# Tastendruckverlaengerer_1.net
KiCad netlist of a schematic drawn in EAGLE
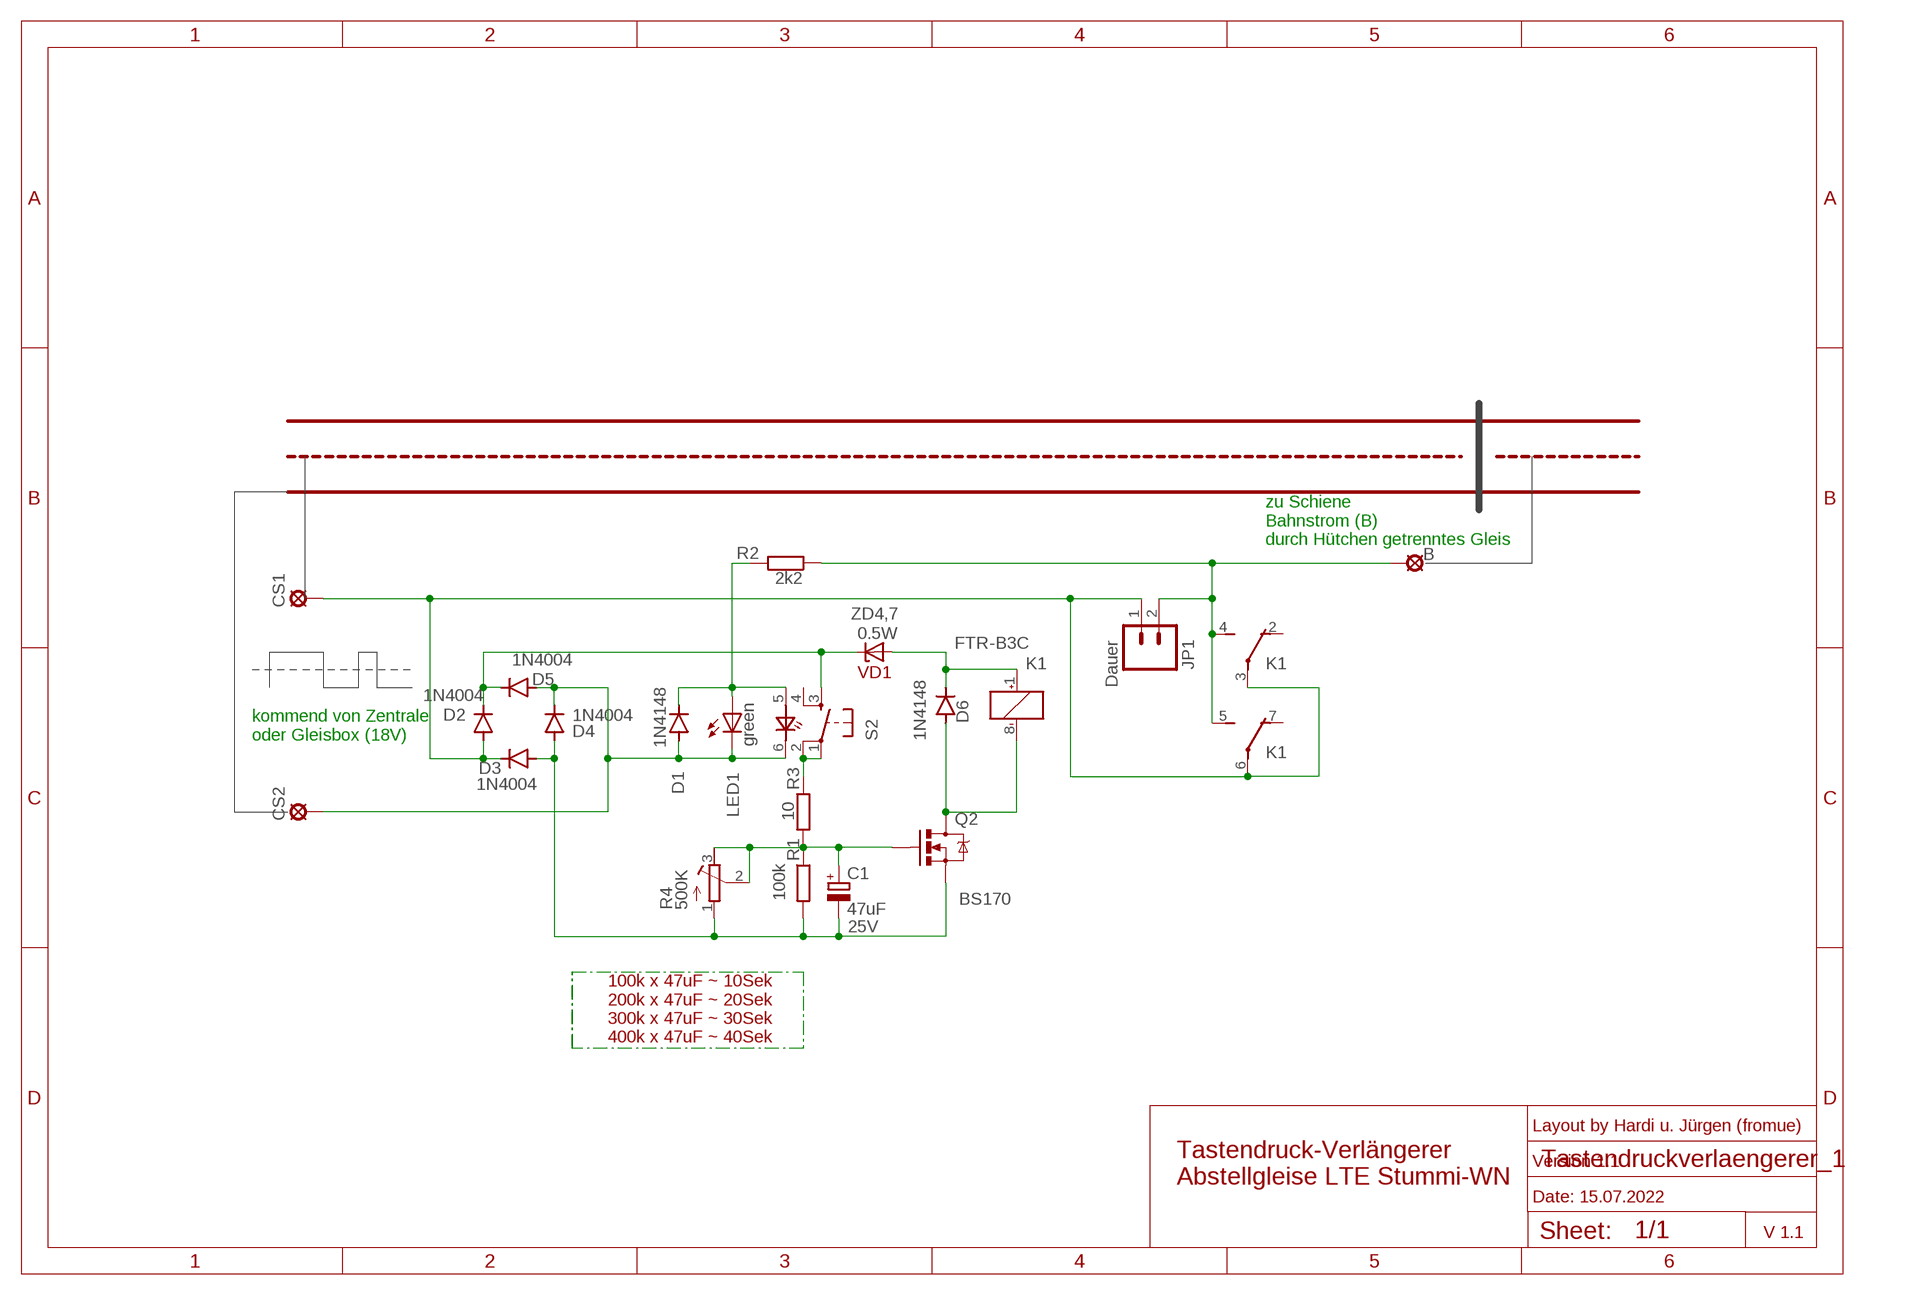
[diagram p0: schematic, sheet 1]

(export (version "E")
  (design (tool "Eeschema 10.0.6"))
  (components
    (comp (ref "B")
      (value "SE14")
      (footprint "eagle-import:SE14")
      (libsource (lib "eagle-import") (part "SE14"))
    )
    (comp (ref "C1")
      (value "47uF")
      (footprint "eagle-import:TT2D5L")
      (fields (field (name "ADD") "25V"))
      (libsource (lib "eagle-import") (part "CPOL-EUTT2D5L"))
    )
    (comp (ref "CS1")
      (value "SE14")
      (footprint "eagle-import:SE14")
      (libsource (lib "eagle-import") (part "SE14"))
    )
    (comp (ref "CS2")
      (value "SE14")
      (footprint "eagle-import:SE14")
      (libsource (lib "eagle-import") (part "SE14"))
    )
    (comp (ref "D1")
      (value "1N4148")
      (footprint "eagle-import:DO35-7")
      (fields (field (name "SPICEPREFIX") "D"))
      (libsource (lib "eagle-import") (part "1N4148DO35-7"))
    )
    (comp (ref "D2")
      (value "1N4004")
      (footprint "eagle-import:DO41-10A")
      (libsource (lib "eagle-import") (part "1N4004DO41-10A"))
    )
    (comp (ref "D3")
      (value "1N4004")
      (footprint "eagle-import:DO41-10A")
      (libsource (lib "eagle-import") (part "1N4004DO41-10A"))
    )
    (comp (ref "D4")
      (value "1N4004")
      (footprint "eagle-import:DO41-10A")
      (libsource (lib "eagle-import") (part "1N4004DO41-10A"))
    )
    (comp (ref "D5")
      (value "1N4004")
      (footprint "eagle-import:DO41-10A")
      (libsource (lib "eagle-import") (part "1N4004DO41-10A"))
    )
    (comp (ref "D6")
      (value "1N4148")
      (footprint "eagle-import:DO35-7")
      (fields (field (name "SPICEPREFIX") "D"))
      (libsource (lib "eagle-import") (part "1N4148DO35-7"))
    )
    (comp (ref "JP1")
      (value "Dauer")
      (footprint "eagle-import:1X02")
      (libsource (lib "eagle-import") (part "M02PTH"))
    )
    (comp (ref "K1")
      (value "FTR-B3C")
      (footprint "eagle-import:FTR-B4C")
      (libsource (lib "eagle-import") (part "FTR-B3C"))
    )
    (comp (ref "LED1")
      (value "green")
      (footprint "eagle-import:LED3MM")
      (libsource (lib "eagle-import") (part "LED3MM"))
    )
    (comp (ref "Q2")
      (value "BS170")
      (footprint "eagle-import:TO-92")
      (libsource (lib "eagle-import") (part "MOSFET-NCHANNELBS170"))
    )
    (comp (ref "R1")
      (value "100k")
      (footprint "eagle-import:0204_7")
      (libsource (lib "eagle-import") (part "R0204/7"))
    )
    (comp (ref "R2")
      (value "2k2")
      (footprint "eagle-import:0204_7")
      (fields (field (name "SPICEPREFIX") "4k7"))
      (libsource (lib "eagle-import") (part "R0204/7"))
    )
    (comp (ref "R3")
      (value "10")
      (footprint "eagle-import:0204_7")
      (libsource (lib "eagle-import") (part "R0204/7"))
    )
    (comp (ref "R4")
      (value "500K")
      (footprint "eagle-import:RTRIM3296W")
      (libsource (lib "eagle-import") (part "R-TRIMM3296W"))
    )
    (comp (ref "S2")
      (value "TASTER_LEDTC-1198-B")
      (footprint "eagle-import:TASTER_LED")
      (libsource (lib "eagle-import") (part "TASTER_LEDTC-1198-B"))
    )
    (comp (ref "VD1")
      (value "ZD4,7")
      (footprint "eagle-import:DIODES-ZENER_DO35-7")
      (fields (field (name "MOUSER") "ZF4.7") (field (name "POWER") "0.5W"))
      (libsource (lib "eagle-import") (part "DIODES-ZENER_?5.6V(1N5232)"))
    )
  )
  (nets
    (net (code "1") (name "Net-(K1A-P)") (class "Default")
      (node (ref "CS1") (pin "MP") (pinfunction "MP_MP") (pintype "passive"))
      (node (ref "D2") (pin "A") (pinfunction "A_A") (pintype "passive"))
      (node (ref "D3") (pin "C") (pinfunction "C_C") (pintype "passive"))
      (node (ref "JP1") (pin "1") (pinfunction "1_1") (pintype "passive"))
      (node (ref "K1") (pin "3") (pinfunction "P_3") (pintype "passive"))
      (node (ref "K1") (pin "6") (pinfunction "P_6") (pintype "passive"))
    )
    (net (code "2") (name "Net-(K1A-S)") (class "Default")
      (node (ref "B") (pin "MP") (pinfunction "MP_MP") (pintype "passive"))
      (node (ref "JP1") (pin "2") (pinfunction "2_2") (pintype "passive"))
      (node (ref "K1") (pin "4") (pinfunction "S_4") (pintype "passive"))
      (node (ref "K1") (pin "5") (pinfunction "S_5") (pintype "passive"))
      (node (ref "R2") (pin "1") (pinfunction "1_1") (pintype "passive"))
    )
    (net (code "3") (name "Net-(K1C-+)") (class "Default")
      (node (ref "D6") (pin "C") (pinfunction "C_C") (pintype "passive"))
      (node (ref "K1") (pin "1") (pinfunction "+_1") (pintype "passive"))
      (node (ref "VD1") (pin "A") (pinfunction "A_A") (pintype "passive"))
    )
    (net (code "4") (name "Net-(K1C--)") (class "Default")
      (node (ref "D6") (pin "A") (pinfunction "A_A") (pintype "passive"))
      (node (ref "K1") (pin "8") (pinfunction "-_8") (pintype "passive"))
      (node (ref "Q2") (pin "1") (pinfunction "D_1") (pintype "passive"))
    )
    (net (code "5") (name "Net-(LED1-C)") (class "Default")
      (node (ref "CS2") (pin "MP") (pinfunction "MP_MP") (pintype "passive"))
      (node (ref "D1") (pin "A") (pinfunction "A_A") (pintype "passive"))
      (node (ref "D4") (pin "C") (pinfunction "C_C") (pintype "passive"))
      (node (ref "D5") (pin "A") (pinfunction "A_A") (pintype "passive"))
      (node (ref "LED1") (pin "K") (pinfunction "C_K") (pintype "passive"))
      (node (ref "S2") (pin "6") (pinfunction "-_6") (pintype "input"))
    )
    (net (code "6") (name "Net-(Q2-G)") (class "Default")
      (node (ref "C1") (pin "+") (pinfunction "+_+") (pintype "passive"))
      (node (ref "Q2") (pin "2") (pinfunction "G_2") (pintype "passive"))
      (node (ref "R1") (pin "1") (pinfunction "1_1") (pintype "passive"))
      (node (ref "R3") (pin "2") (pinfunction "2_2") (pintype "passive"))
      (node (ref "R4") (pin "2") (pinfunction "S_2") (pintype "passive"))
      (node (ref "R4") (pin "3") (pinfunction "E_3") (pintype "passive"))
    )
    (net (code "7") (name "Net-(Q2-S)") (class "Default")
      (node (ref "C1") (pin "-") (pinfunction "-_-") (pintype "passive"))
      (node (ref "D3") (pin "A") (pinfunction "A_A") (pintype "passive"))
      (node (ref "D4") (pin "A") (pinfunction "A_A") (pintype "passive"))
      (node (ref "Q2") (pin "3") (pinfunction "S_3") (pintype "passive"))
      (node (ref "R1") (pin "2") (pinfunction "2_2") (pintype "passive"))
      (node (ref "R4") (pin "1") (pinfunction "A_1") (pintype "passive"))
    )
    (net (code "8") (name "Net-(S2-+)") (class "Default")
      (node (ref "D1") (pin "C") (pinfunction "C_C") (pintype "passive"))
      (node (ref "LED1") (pin "A") (pinfunction "A_A") (pintype "passive"))
      (node (ref "R2") (pin "2") (pinfunction "2_2") (pintype "passive"))
      (node (ref "S2") (pin "5") (pinfunction "+_5") (pintype "input"))
    )
    (net (code "9") (name "Net-(S2-P)") (class "Default")
      (node (ref "R3") (pin "1") (pinfunction "1_1") (pintype "passive"))
      (node (ref "S2") (pin "1") (pinfunction "P_1") (pintype "passive"))
      (node (ref "S2") (pin "2") (pinfunction "P1_2") (pintype "passive"))
    )
    (net (code "10") (name "Net-(S2-S)") (class "Default")
      (node (ref "D2") (pin "C") (pinfunction "C_C") (pintype "passive"))
      (node (ref "D5") (pin "C") (pinfunction "C_C") (pintype "passive"))
      (node (ref "S2") (pin "3") (pinfunction "S_3") (pintype "passive"))
      (node (ref "VD1") (pin "C") (pinfunction "C_C") (pintype "passive"))
    )
    (net (code "11") (name "unconnected-(K1A-O-Pad2)") (class "Default")
      (node (ref "K1") (pin "2") (pinfunction "O_2") (pintype "passive"))
    )
    (net (code "12") (name "unconnected-(K1B-O-Pad7)") (class "Default")
      (node (ref "K1") (pin "7") (pinfunction "O_7") (pintype "passive"))
    )
    (net (code "13") (name "unconnected-(S2-S1-Pad4)") (class "Default")
      (node (ref "S2") (pin "4") (pinfunction "S1_4") (pintype "passive"))
    )
  )
)
